# miavita.net
KiCad netlist of a schematic drawn in EAGLE
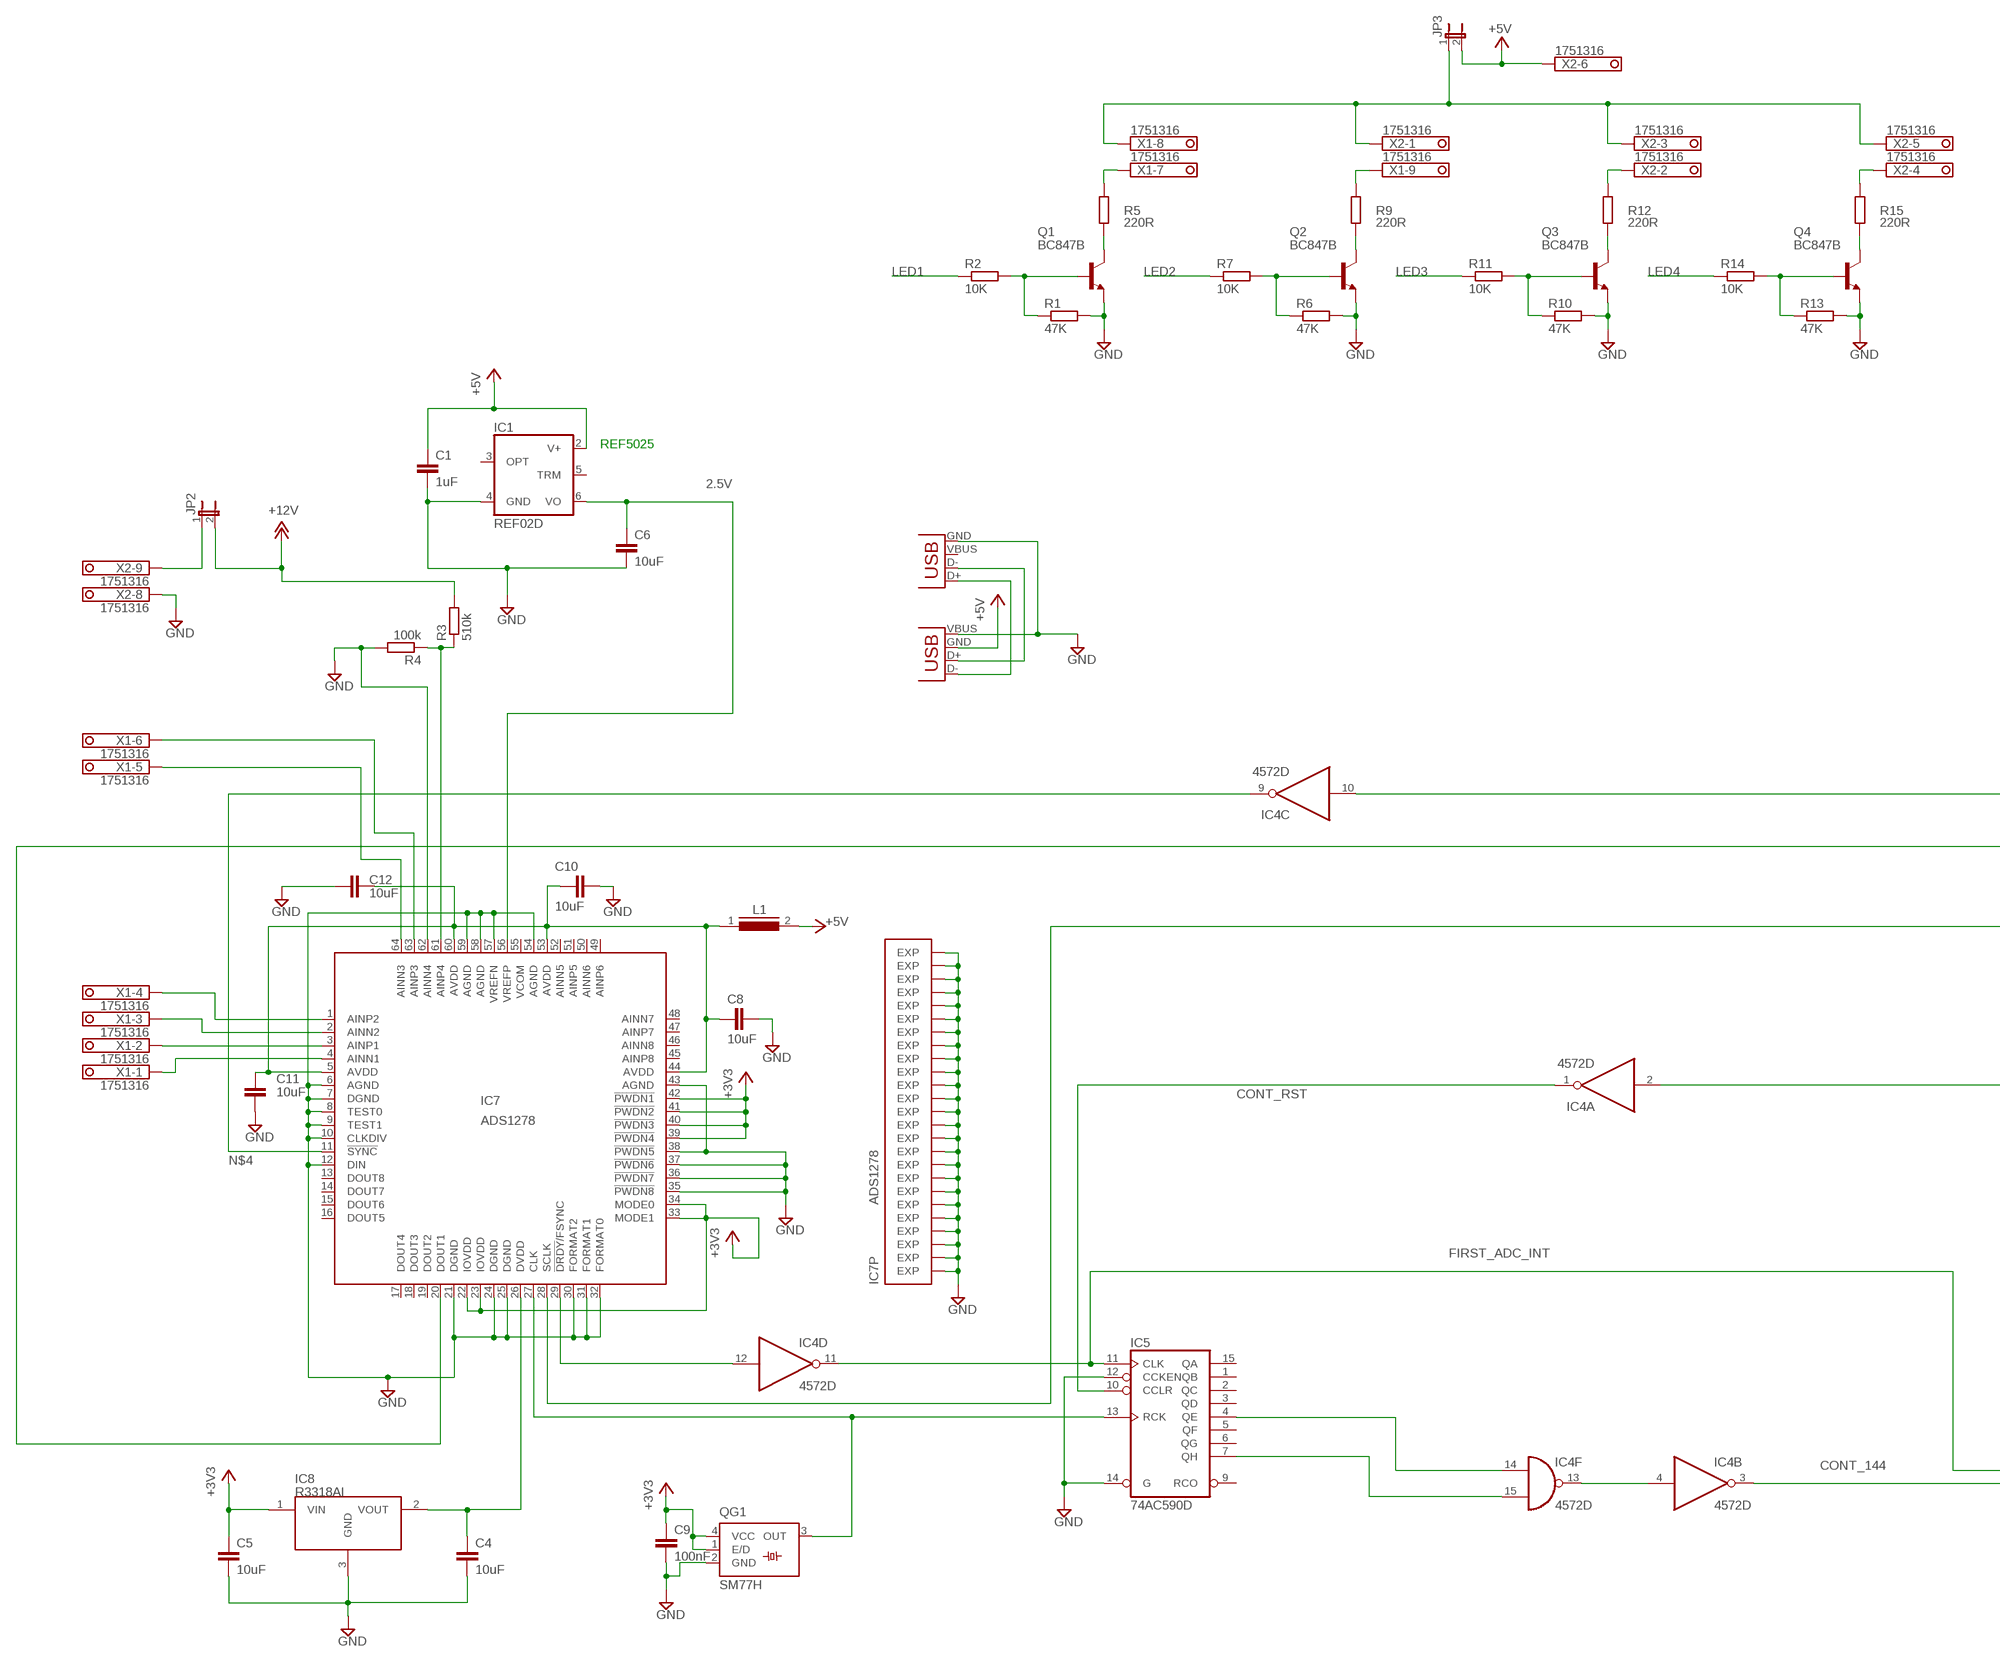
[diagram p0: schematic, sheet 1, part 1 of 2]
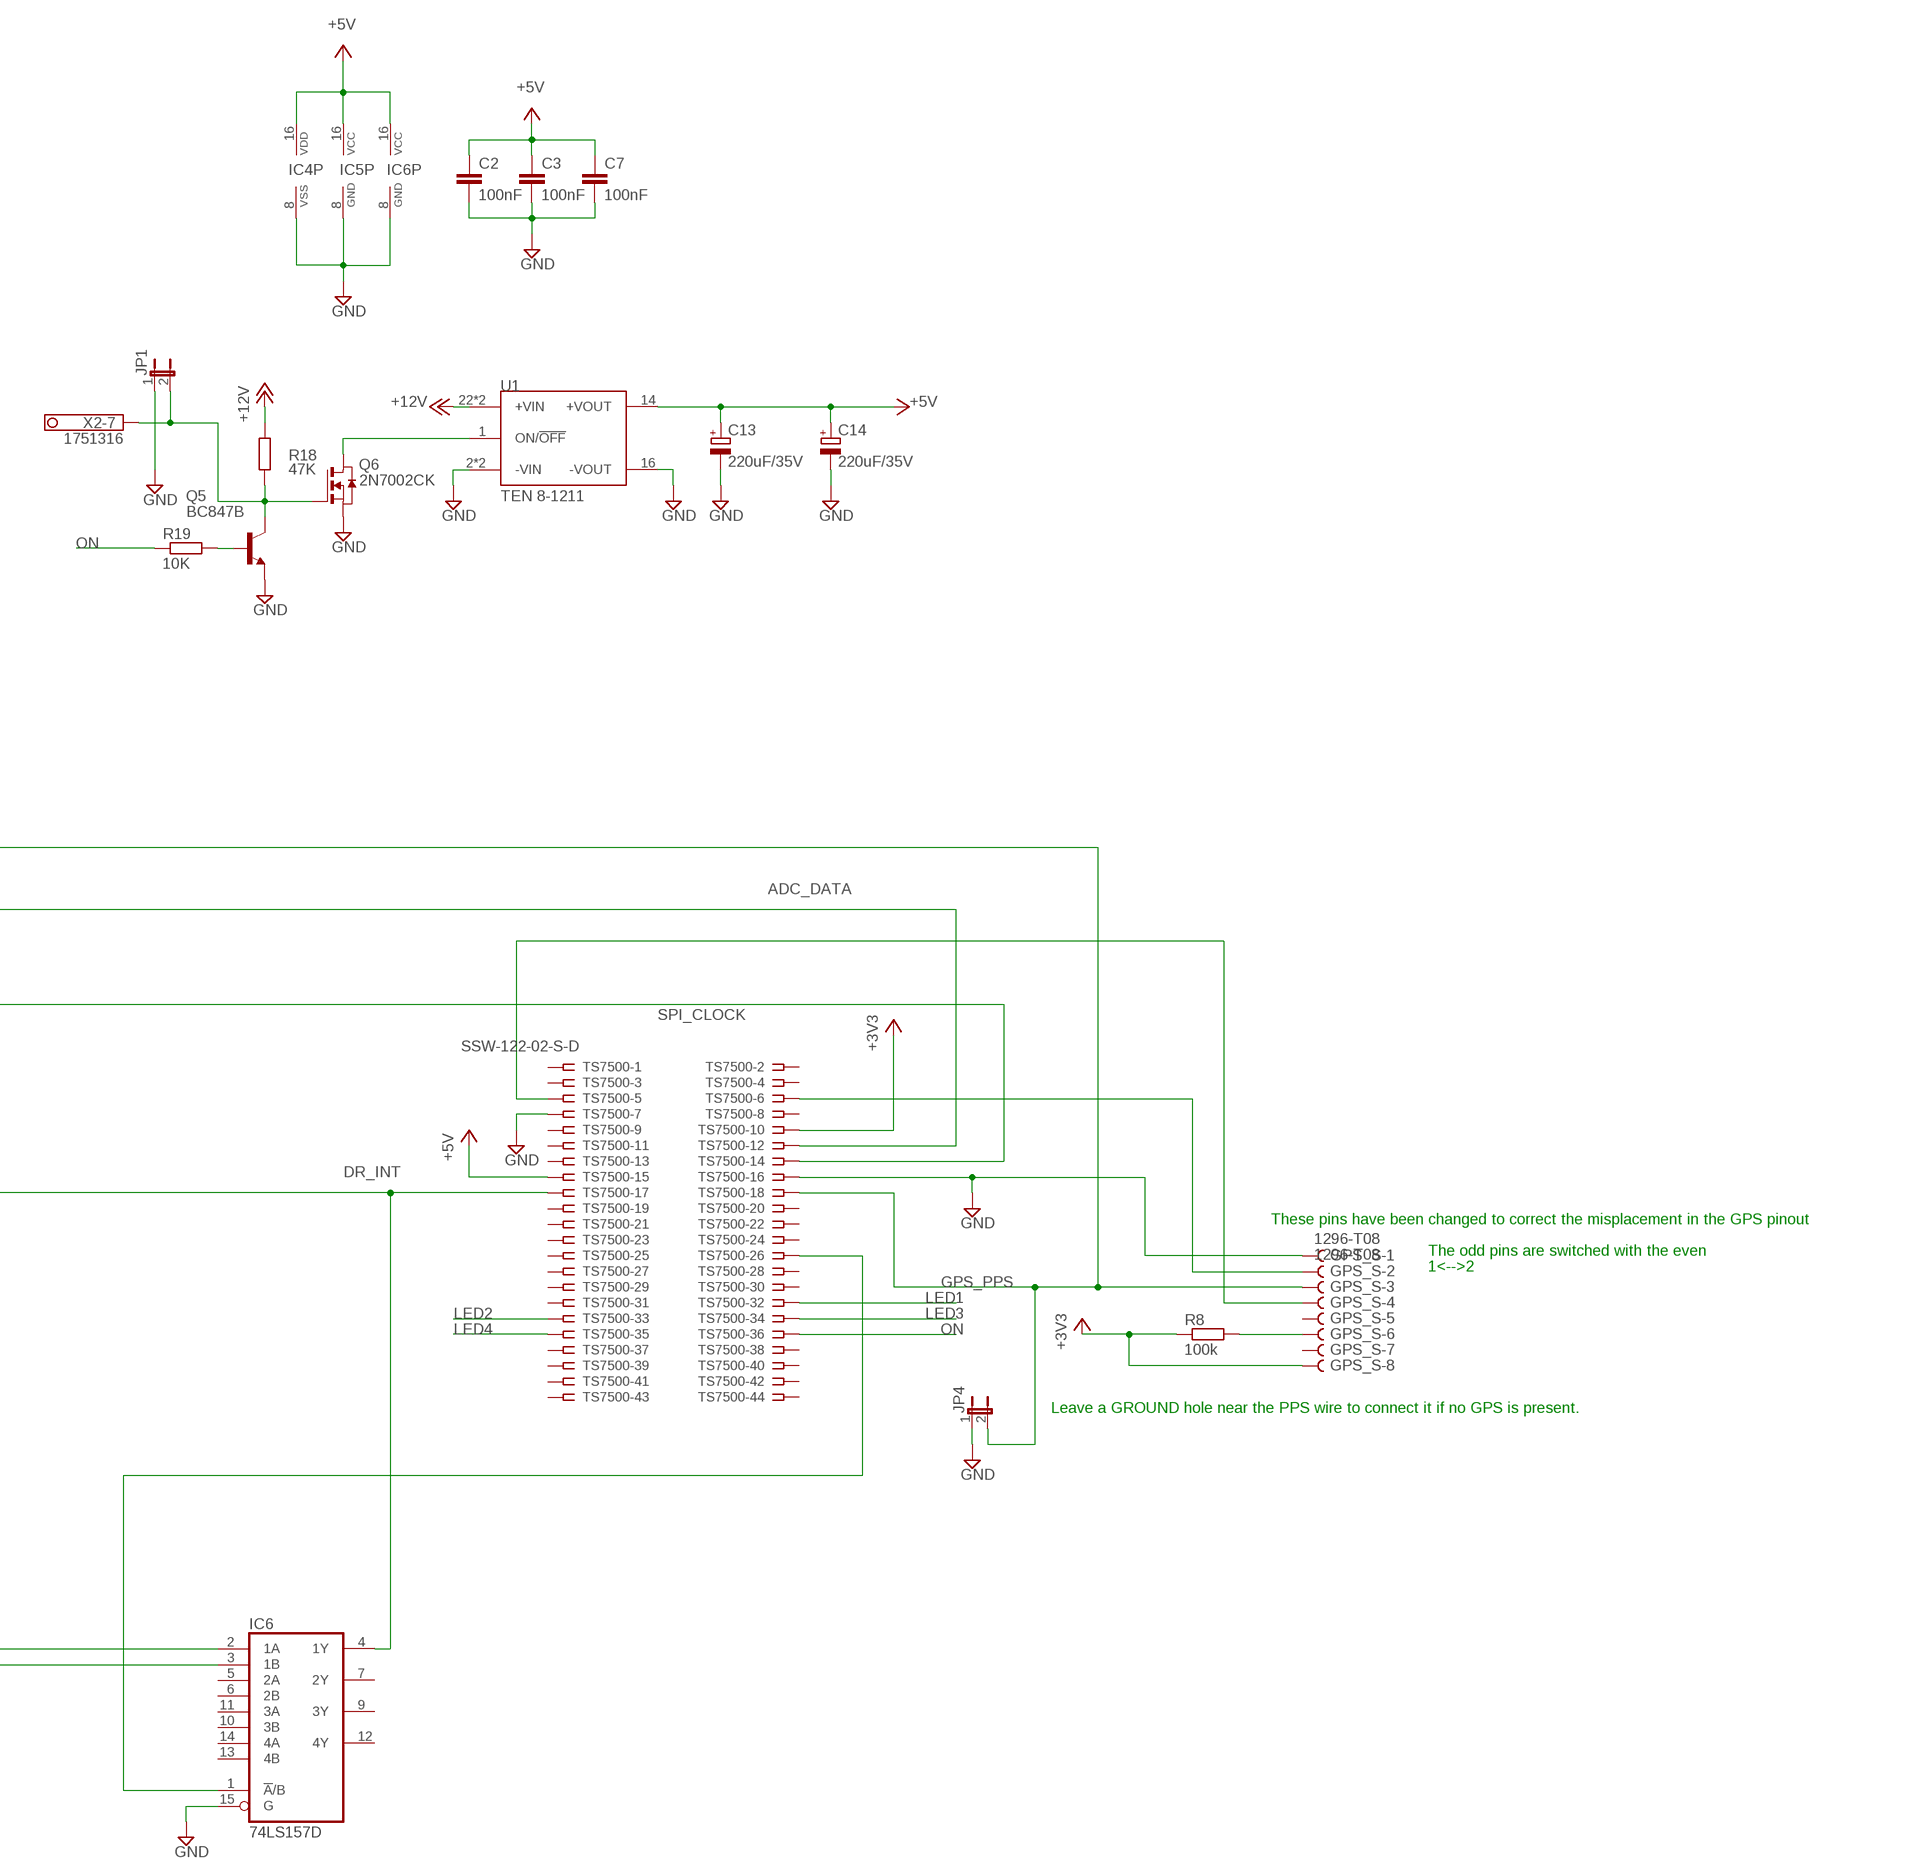
[diagram p1: schematic, sheet 1, part 2 of 2]

(export (version "E")
  (design (tool "Eeschema 10.0.6"))
  (components
    (comp (ref "C1")
      (value "1uF")
      (footprint "eagle-import:C0603")
      (libsource (lib "eagle-import") (part "C-EUC0603"))
    )
    (comp (ref "C2")
      (value "100nF")
      (footprint "eagle-import:C0603")
      (libsource (lib "eagle-import") (part "C-EUC0603"))
    )
    (comp (ref "C3")
      (value "100nF")
      (footprint "eagle-import:C0603")
      (libsource (lib "eagle-import") (part "C-EUC0603"))
    )
    (comp (ref "C4")
      (value "10uF")
      (footprint "eagle-import:C1210")
      (libsource (lib "eagle-import") (part "C-EUC1210"))
    )
    (comp (ref "C5")
      (value "10uF")
      (footprint "eagle-import:C1210")
      (libsource (lib "eagle-import") (part "C-EUC1210"))
    )
    (comp (ref "C6")
      (value "10uF")
      (footprint "eagle-import:C1210")
      (libsource (lib "eagle-import") (part "C-EUC1210"))
    )
    (comp (ref "C7")
      (value "100nF")
      (footprint "eagle-import:C0603")
      (libsource (lib "eagle-import") (part "C-EUC0603"))
    )
    (comp (ref "C8")
      (value "10uF")
      (footprint "eagle-import:C0805")
      (libsource (lib "eagle-import") (part "C-EUC0805"))
    )
    (comp (ref "C9")
      (value "100nF")
      (footprint "eagle-import:C0603")
      (libsource (lib "eagle-import") (part "C-EUC0603"))
    )
    (comp (ref "C10")
      (value "10uF")
      (footprint "eagle-import:C0805")
      (libsource (lib "eagle-import") (part "C-EUC0805"))
    )
    (comp (ref "C11")
      (value "10uF")
      (footprint "eagle-import:C0805")
      (libsource (lib "eagle-import") (part "C-EUC0805"))
    )
    (comp (ref "C12")
      (value "10uF")
      (footprint "eagle-import:C0805")
      (libsource (lib "eagle-import") (part "C-EUC0805"))
    )
    (comp (ref "C13")
      (value "220uF/35V")
      (footprint "eagle-import:UD-10X10_NICHICON")
      (libsource (lib "eagle-import") (part "CPOL-EUUD-10X10"))
    )
    (comp (ref "C14")
      (value "220uF/35V")
      (footprint "eagle-import:UD-10X10_NICHICON")
      (libsource (lib "eagle-import") (part "CPOL-EUUD-10X10"))
    )
    (comp (ref "GPS_S")
      (value "1296-T08")
      (footprint "eagle-import:1296-08")
      (libsource (lib "eagle-import") (part "1296-T08"))
    )
    (comp (ref "IC1")
      (value "REF02D")
      (footprint "eagle-import:SO08")
      (libsource (lib "eagle-import") (part "REF02D"))
    )
    (comp (ref "IC4")
      (value "4572D")
      (footprint "eagle-import:SO16")
      (libsource (lib "eagle-import") (part "4572D"))
    )
    (comp (ref "IC5")
      (value "74AC590D")
      (footprint "eagle-import:SO16")
      (libsource (lib "eagle-import") (part "74590DAC"))
    )
    (comp (ref "IC6")
      (value "74LS157D")
      (footprint "eagle-import:SO16")
      (libsource (lib "eagle-import") (part "74157DLS"))
    )
    (comp (ref "IC7")
      (value "ADS1278")
      (footprint "eagle-import:HTQFP-64-PAP")
      (fields (field (name "MPN") "ADS1278IPAPT"))
      (libsource (lib "eagle-import") (part "ADS1278"))
    )
    (comp (ref "IC8")
      (value "R3318AI")
      (footprint "eagle-import:SOT23")
      (libsource (lib "eagle-import") (part "MCP1525TTT-I/"))
    )
    (comp (ref "JP1")
      (value "JP1E")
      (footprint "eagle-import:JP1")
      (libsource (lib "eagle-import") (part "JP1E"))
    )
    (comp (ref "JP2")
      (value "JP1E")
      (footprint "eagle-import:JP1")
      (libsource (lib "eagle-import") (part "JP1E"))
    )
    (comp (ref "JP3")
      (value "JP1E")
      (footprint "eagle-import:JP1")
      (libsource (lib "eagle-import") (part "JP1E"))
    )
    (comp (ref "JP4")
      (value "JP1E")
      (footprint "eagle-import:JP1")
      (libsource (lib "eagle-import") (part "JP1E"))
    )
    (comp (ref "L1")
      (value "FAIR-RITE_2506031027Y0")
      (footprint "eagle-import:L0603")
      (libsource (lib "eagle-import") (part "FAIR-RITE_251027Y00603"))
    )
    (comp (ref "Q1")
      (value "BC847B")
      (footprint "eagle-import:SOT23")
      (libsource (lib "eagle-import") (part "BC847SMDBLT1"))
    )
    (comp (ref "Q2")
      (value "BC847B")
      (footprint "eagle-import:SOT23")
      (libsource (lib "eagle-import") (part "BC847SMDBLT1"))
    )
    (comp (ref "Q3")
      (value "BC847B")
      (footprint "eagle-import:SOT23")
      (libsource (lib "eagle-import") (part "BC847SMDBLT1"))
    )
    (comp (ref "Q4")
      (value "BC847B")
      (footprint "eagle-import:SOT23")
      (libsource (lib "eagle-import") (part "BC847SMDBLT1"))
    )
    (comp (ref "Q5")
      (value "BC847B")
      (footprint "eagle-import:SOT23")
      (libsource (lib "eagle-import") (part "BC847SMDBLT1"))
    )
    (comp (ref "Q6")
      (value "2N7002CK")
      (footprint "eagle-import:SOT23")
      (libsource (lib "eagle-import") (part "2N7002CK"))
    )
    (comp (ref "QG1")
      (value "SM77H")
      (footprint "eagle-import:SM77H")
      (libsource (lib "eagle-import") (part "SM77H"))
    )
    (comp (ref "R1")
      (value "47K")
      (footprint "eagle-import:R0603")
      (libsource (lib "eagle-import") (part "R-EU_R0603"))
    )
    (comp (ref "R2")
      (value "10K")
      (footprint "eagle-import:R0603")
      (libsource (lib "eagle-import") (part "R-EU_R0603"))
    )
    (comp (ref "R3")
      (value "510k")
      (footprint "eagle-import:R0603")
      (libsource (lib "eagle-import") (part "R-EU_R0603"))
    )
    (comp (ref "R4")
      (value "100k")
      (footprint "eagle-import:R0603")
      (libsource (lib "eagle-import") (part "R-EU_R0603"))
    )
    (comp (ref "R5")
      (value "220R")
      (footprint "eagle-import:R0603")
      (libsource (lib "eagle-import") (part "R-EU_R0603"))
    )
    (comp (ref "R6")
      (value "47K")
      (footprint "eagle-import:R0603")
      (libsource (lib "eagle-import") (part "R-EU_R0603"))
    )
    (comp (ref "R7")
      (value "10K")
      (footprint "eagle-import:R0603")
      (libsource (lib "eagle-import") (part "R-EU_R0603"))
    )
    (comp (ref "R8")
      (value "100k")
      (footprint "eagle-import:R0603")
      (libsource (lib "eagle-import") (part "R-EU_R0603"))
    )
    (comp (ref "R9")
      (value "220R")
      (footprint "eagle-import:R0603")
      (libsource (lib "eagle-import") (part "R-EU_R0603"))
    )
    (comp (ref "R10")
      (value "47K")
      (footprint "eagle-import:R0603")
      (libsource (lib "eagle-import") (part "R-EU_R0603"))
    )
    (comp (ref "R11")
      (value "10K")
      (footprint "eagle-import:R0603")
      (libsource (lib "eagle-import") (part "R-EU_R0603"))
    )
    (comp (ref "R12")
      (value "220R")
      (footprint "eagle-import:R0603")
      (libsource (lib "eagle-import") (part "R-EU_R0603"))
    )
    (comp (ref "R13")
      (value "47K")
      (footprint "eagle-import:R0603")
      (libsource (lib "eagle-import") (part "R-EU_R0603"))
    )
    (comp (ref "R14")
      (value "10K")
      (footprint "eagle-import:R0603")
      (libsource (lib "eagle-import") (part "R-EU_R0603"))
    )
    (comp (ref "R15")
      (value "220R")
      (footprint "eagle-import:R0603")
      (libsource (lib "eagle-import") (part "R-EU_R0603"))
    )
    (comp (ref "R18")
      (value "47K")
      (footprint "eagle-import:R0603")
      (libsource (lib "eagle-import") (part "R-EU_R0603"))
    )
    (comp (ref "R19")
      (value "10K")
      (footprint "eagle-import:R0603")
      (libsource (lib "eagle-import") (part "R-EU_R0603"))
    )
    (comp (ref "TS7500")
      (value "SSW-122-02-S-D")
      (footprint "eagle-import:SSW-122-02-S-D")
      (libsource (lib "eagle-import") (part "SSW-122-02-S-D"))
    )
    (comp (ref "U1")
      (value "TEN 8-1211")
      (footprint "eagle-import:TRACOPOWER_TEN-8-SERIES")
      (libsource (lib "eagle-import") (part "TRACOPOWER_TEN-8-1211"))
    )
    (comp (ref "USBA")
      (value "USB-A-H")
      (footprint "eagle-import:USB-A-H")
      (libsource (lib "eagle-import") (part "USB-A-H"))
    )
    (comp (ref "USBB")
      (value "USBPTH")
      (footprint "eagle-import:USB-B-PTH")
      (libsource (lib "eagle-import") (part "USBPTH"))
    )
    (comp (ref "X1")
      (value "1751316")
      (footprint "eagle-import:1751316")
      (libsource (lib "eagle-import") (part "1751316"))
    )
    (comp (ref "X2")
      (value "1751316")
      (footprint "eagle-import:1751316")
      (libsource (lib "eagle-import") (part "1751316"))
    )
  )
  (nets
    (net (code "1") (name "+3V3") (class "Default")
      (node (ref "C5") (pin "1") (pinfunction "1_1") (pintype "passive"))
      (node (ref "C9") (pin "1") (pinfunction "1_1") (pintype "passive"))
      (node (ref "GPS_S") (pin "8") (pinfunction "B_8") (pintype "passive"))
      (node (ref "IC7") (pin "22") (pinfunction "IOVDD_22") (pintype "power_in"))
      (node (ref "IC7") (pin "23") (pinfunction "IOVDD_23") (pintype "power_in"))
      (node (ref "IC7") (pin "33") (pinfunction "MODE1_33") (pintype "input"))
      (node (ref "IC7") (pin "34") (pinfunction "MODE0_34") (pintype "input"))
      (node (ref "IC7") (pin "39") (pinfunction "~{PWDN4}_39") (pintype "input"))
      (node (ref "IC7") (pin "40") (pinfunction "~{PWDN3}_40") (pintype "input"))
      (node (ref "IC7") (pin "41") (pinfunction "~{PWDN2}_41") (pintype "input"))
      (node (ref "IC7") (pin "42") (pinfunction "~{PWDN1}_42") (pintype "input"))
      (node (ref "IC8") (pin "1") (pinfunction "VIN_1") (pintype "power_in"))
      (node (ref "QG1") (pin "1") (pinfunction "E/D_1") (pintype "input"))
      (node (ref "QG1") (pin "4") (pinfunction "VCC_4") (pintype "power_in"))
      (node (ref "R8") (pin "1") (pinfunction "1_1") (pintype "passive"))
      (node (ref "TS7500") (pin "10") (pinfunction "1_10") (pintype "passive"))
    )
    (net (code "2") (name "+5V") (class "Default")
      (node (ref "C1") (pin "1") (pinfunction "1_1") (pintype "passive"))
      (node (ref "C13") (pin "+") (pinfunction "+_+") (pintype "passive"))
      (node (ref "C14") (pin "+") (pinfunction "+_+") (pintype "passive"))
      (node (ref "C2") (pin "1") (pinfunction "1_1") (pintype "passive"))
      (node (ref "C3") (pin "1") (pinfunction "1_1") (pintype "passive"))
      (node (ref "C7") (pin "1") (pinfunction "1_1") (pintype "passive"))
      (node (ref "IC1") (pin "2") (pinfunction "V+_2") (pintype "power_in"))
      (node (ref "IC4") (pin "16") (pinfunction "VDD_16") (pintype "power_in"))
      (node (ref "IC5") (pin "16") (pinfunction "VCC_16") (pintype "power_in"))
      (node (ref "IC6") (pin "16") (pinfunction "VCC_16") (pintype "power_in"))
      (node (ref "JP3") (pin "2") (pinfunction "2_2") (pintype "passive"))
      (node (ref "L1") (pin "2") (pinfunction "2_2") (pintype "passive"))
      (node (ref "TS7500") (pin "15") (pinfunction "1_15") (pintype "passive"))
      (node (ref "U1") (pin "14") (pinfunction "+VOUT_14") (pintype "bidirectional"))
      (node (ref "USBA") (pin "GND") (pinfunction "VBUS_GND") (pintype "bidirectional"))
      (node (ref "X2") (pin "6") (pinfunction "K_6") (pintype "passive"))
    )
    (net (code "3") (name "+12V") (class "Default")
      (node (ref "JP2") (pin "2") (pinfunction "2_2") (pintype "passive"))
      (node (ref "R18") (pin "1") (pinfunction "1_1") (pintype "passive"))
      (node (ref "R3") (pin "2") (pinfunction "2_2") (pintype "passive"))
      (node (ref "U1") (pin "22") (pinfunction "+VIN_22") (pintype "power_in"))
      (node (ref "U1") (pin "23") (pinfunction "+VIN_23") (pintype "power_in"))
    )
    (net (code "4") (name "/2.5V") (class "Default")
      (node (ref "C6") (pin "1") (pinfunction "1_1") (pintype "passive"))
      (node (ref "IC1") (pin "6") (pinfunction "VO_6") (pintype "output"))
      (node (ref "IC7") (pin "56") (pinfunction "VREFP_56") (pintype "input"))
    )
    (net (code "5") (name "/ADC_DATA") (class "Default")
      (node (ref "IC7") (pin "20") (pinfunction "DOUT1_20") (pintype "output"))
      (node (ref "TS7500") (pin "12") (pinfunction "1_12") (pintype "passive"))
    )
    (net (code "6") (name "/CONT_144") (class "Default")
      (node (ref "IC4") (pin "3") (pinfunction "O_3") (pintype "output"))
      (node (ref "IC6") (pin "3") (pinfunction "1B_3") (pintype "input"))
    )
    (net (code "7") (name "/CONT_RST") (class "Default")
      (node (ref "IC4") (pin "1") (pinfunction "O_1") (pintype "output"))
      (node (ref "IC5") (pin "10") (pinfunction "CCLR_10") (pintype "input"))
    )
    (net (code "8") (name "/DR_INT") (class "Default")
      (node (ref "IC4") (pin "2") (pinfunction "I_2") (pintype "input"))
      (node (ref "IC6") (pin "4") (pinfunction "1Y_4") (pintype "output"))
      (node (ref "TS7500") (pin "17") (pinfunction "1_17") (pintype "passive"))
    )
    (net (code "9") (name "/FIRST_ADC_INT") (class "Default")
      (node (ref "IC4") (pin "11") (pinfunction "O_11") (pintype "output"))
      (node (ref "IC5") (pin "11") (pinfunction "CLK_11") (pintype "input"))
      (node (ref "IC6") (pin "2") (pinfunction "1A_2") (pintype "input"))
    )
    (net (code "10") (name "/GPS_PPS") (class "Default")
      (node (ref "GPS_S") (pin "3") (pinfunction "B_3") (pintype "passive"))
      (node (ref "IC4") (pin "10") (pinfunction "I_10") (pintype "input"))
      (node (ref "JP4") (pin "2") (pinfunction "2_2") (pintype "passive"))
      (node (ref "TS7500") (pin "18") (pinfunction "1_18") (pintype "passive"))
    )
    (net (code "11") (name "/LED1") (class "Default")
      (node (ref "R2") (pin "1") (pinfunction "1_1") (pintype "passive"))
      (node (ref "TS7500") (pin "32") (pinfunction "1_32") (pintype "passive"))
    )
    (net (code "12") (name "/LED2") (class "Default")
      (node (ref "R7") (pin "1") (pinfunction "1_1") (pintype "passive"))
      (node (ref "TS7500") (pin "33") (pinfunction "1_33") (pintype "passive"))
    )
    (net (code "13") (name "/LED3") (class "Default")
      (node (ref "R11") (pin "1") (pinfunction "1_1") (pintype "passive"))
      (node (ref "TS7500") (pin "34") (pinfunction "1_34") (pintype "passive"))
    )
    (net (code "14") (name "/LED4") (class "Default")
      (node (ref "R14") (pin "1") (pinfunction "1_1") (pintype "passive"))
      (node (ref "TS7500") (pin "35") (pinfunction "1_35") (pintype "passive"))
    )
    (net (code "15") (name "/N$4") (class "Default")
      (node (ref "IC4") (pin "9") (pinfunction "O_9") (pintype "output"))
      (node (ref "IC7") (pin "11") (pinfunction "~{SYNC}_11") (pintype "input"))
    )
    (net (code "16") (name "/ON") (class "Default")
      (node (ref "R19") (pin "1") (pinfunction "1_1") (pintype "passive"))
      (node (ref "TS7500") (pin "36") (pinfunction "1_36") (pintype "passive"))
    )
    (net (code "17") (name "/SPI_CLOCK") (class "Default")
      (node (ref "IC7") (pin "28") (pinfunction "SCLK_28") (pintype "bidirectional"))
      (node (ref "TS7500") (pin "14") (pinfunction "1_14") (pintype "passive"))
    )
    (net (code "18") (name "GND") (class "Default")
      (node (ref "C1") (pin "2") (pinfunction "2_2") (pintype "passive"))
      (node (ref "C10") (pin "2") (pinfunction "2_2") (pintype "passive"))
      (node (ref "C11") (pin "2") (pinfunction "2_2") (pintype "passive"))
      (node (ref "C12") (pin "2") (pinfunction "2_2") (pintype "passive"))
      (node (ref "C13") (pin "-") (pinfunction "-_-") (pintype "passive"))
      (node (ref "C14") (pin "-") (pinfunction "-_-") (pintype "passive"))
      (node (ref "C2") (pin "2") (pinfunction "2_2") (pintype "passive"))
      (node (ref "C3") (pin "2") (pinfunction "2_2") (pintype "passive"))
      (node (ref "C4") (pin "2") (pinfunction "2_2") (pintype "passive"))
      (node (ref "C5") (pin "2") (pinfunction "2_2") (pintype "passive"))
      (node (ref "C6") (pin "2") (pinfunction "2_2") (pintype "passive"))
      (node (ref "C7") (pin "2") (pinfunction "2_2") (pintype "passive"))
      (node (ref "C8") (pin "2") (pinfunction "2_2") (pintype "passive"))
      (node (ref "C9") (pin "2") (pinfunction "2_2") (pintype "passive"))
      (node (ref "GPS_S") (pin "1") (pinfunction "B_1") (pintype "passive"))
      (node (ref "IC1") (pin "4") (pinfunction "GND_4") (pintype "power_in"))
      (node (ref "IC4") (pin "8") (pinfunction "VSS_8") (pintype "power_in"))
      (node (ref "IC5") (pin "12") (pinfunction "CCKEN_12") (pintype "input"))
      (node (ref "IC5") (pin "14") (pinfunction "G_14") (pintype "input"))
      (node (ref "IC5") (pin "8") (pinfunction "GND_8") (pintype "power_in"))
      (node (ref "IC6") (pin "15") (pinfunction "G_15") (pintype "input"))
      (node (ref "IC6") (pin "8") (pinfunction "GND_8") (pintype "power_in"))
      (node (ref "IC7") (pin "10") (pinfunction "CLKDIV_10") (pintype "input"))
      (node (ref "IC7") (pin "12") (pinfunction "DIN_12") (pintype "input"))
      (node (ref "IC7") (pin "21") (pinfunction "DGND_21") (pintype "power_in"))
      (node (ref "IC7") (pin "24") (pinfunction "DGND_24") (pintype "power_in"))
      (node (ref "IC7") (pin "25") (pinfunction "DGND_25") (pintype "power_in"))
      (node (ref "IC7") (pin "30") (pinfunction "FORMAT2_30") (pintype "input"))
      (node (ref "IC7") (pin "31") (pinfunction "FORMAT1_31") (pintype "input"))
      (node (ref "IC7") (pin "32") (pinfunction "FORMAT0_32") (pintype "input"))
      (node (ref "IC7") (pin "35") (pinfunction "~{PWDN8}_35") (pintype "input"))
      (node (ref "IC7") (pin "36") (pinfunction "~{PWDN7}_36") (pintype "input"))
      (node (ref "IC7") (pin "37") (pinfunction "~{PWDN6}_37") (pintype "input"))
      (node (ref "IC7") (pin "38") (pinfunction "~{PWDN5}_38") (pintype "input"))
      (node (ref "IC7") (pin "43") (pinfunction "AGND_43") (pintype "power_in"))
      (node (ref "IC7") (pin "54") (pinfunction "AGND_54") (pintype "power_in"))
      (node (ref "IC7") (pin "57") (pinfunction "VREFN_57") (pintype "input"))
      (node (ref "IC7") (pin "58") (pinfunction "AGND_58") (pintype "power_in"))
      (node (ref "IC7") (pin "59") (pinfunction "AGND_59") (pintype "power_in"))
      (node (ref "IC7") (pin "6") (pinfunction "AGND_6") (pintype "power_in"))
      (node (ref "IC7") (pin "62") (pinfunction "AINN4_62") (pintype "input"))
      (node (ref "IC7") (pin "7") (pinfunction "DGND_7") (pintype "power_in"))
      (node (ref "IC7") (pin "8") (pinfunction "TEST0_8") (pintype "input"))
      (node (ref "IC7") (pin "9") (pinfunction "TEST1_9") (pintype "input"))
      (node (ref "IC7") (pin "EXP1") (pinfunction "EXP_EXP1") (pintype "passive"))
      (node (ref "IC7") (pin "EXP10") (pinfunction "EXP_EXP10") (pintype "passive"))
      (node (ref "IC7") (pin "EXP11") (pinfunction "EXP_EXP11") (pintype "passive"))
      (node (ref "IC7") (pin "EXP12") (pinfunction "EXP_EXP12") (pintype "passive"))
      (node (ref "IC7") (pin "EXP13") (pinfunction "EXP_EXP13") (pintype "passive"))
      (node (ref "IC7") (pin "EXP14") (pinfunction "EXP_EXP14") (pintype "passive"))
      (node (ref "IC7") (pin "EXP15") (pinfunction "EXP_EXP15") (pintype "passive"))
      (node (ref "IC7") (pin "EXP16") (pinfunction "EXP_EXP16") (pintype "passive"))
      (node (ref "IC7") (pin "EXP17") (pinfunction "EXP_EXP17") (pintype "passive"))
      (node (ref "IC7") (pin "EXP18") (pinfunction "EXP_EXP18") (pintype "passive"))
      (node (ref "IC7") (pin "EXP19") (pinfunction "EXP_EXP19") (pintype "passive"))
      (node (ref "IC7") (pin "EXP2") (pinfunction "EXP_EXP2") (pintype "passive"))
      (node (ref "IC7") (pin "EXP20") (pinfunction "EXP_EXP20") (pintype "passive"))
      (node (ref "IC7") (pin "EXP21") (pinfunction "EXP_EXP21") (pintype "passive"))
      (node (ref "IC7") (pin "EXP22") (pinfunction "EXP_EXP22") (pintype "passive"))
      (node (ref "IC7") (pin "EXP23") (pinfunction "EXP_EXP23") (pintype "passive"))
      (node (ref "IC7") (pin "EXP24") (pinfunction "EXP_EXP24") (pintype "passive"))
      (node (ref "IC7") (pin "EXP25") (pinfunction "EXP_EXP25") (pintype "passive"))
      (node (ref "IC7") (pin "EXP3") (pinfunction "EXP_EXP3") (pintype "passive"))
      (node (ref "IC7") (pin "EXP4") (pinfunction "EXP_EXP4") (pintype "passive"))
      (node (ref "IC7") (pin "EXP5") (pinfunction "EXP_EXP5") (pintype "passive"))
      (node (ref "IC7") (pin "EXP6") (pinfunction "EXP_EXP6") (pintype "passive"))
      (node (ref "IC7") (pin "EXP7") (pinfunction "EXP_EXP7") (pintype "passive"))
      (node (ref "IC7") (pin "EXP8") (pinfunction "EXP_EXP8") (pintype "passive"))
      (node (ref "IC7") (pin "EXP9") (pinfunction "EXP_EXP9") (pintype "passive"))
      (node (ref "IC8") (pin "3") (pinfunction "GND_3") (pintype "power_in"))
      (node (ref "JP1") (pin "1") (pinfunction "1_1") (pintype "passive"))
      (node (ref "JP4") (pin "1") (pinfunction "1_1") (pintype "passive"))
      (node (ref "Q1") (pin "2") (pinfunction "E_2") (pintype "passive"))
      (node (ref "Q2") (pin "2") (pinfunction "E_2") (pintype "passive"))
      (node (ref "Q3") (pin "2") (pinfunction "E_2") (pintype "passive"))
      (node (ref "Q4") (pin "2") (pinfunction "E_2") (pintype "passive"))
      (node (ref "Q5") (pin "2") (pinfunction "E_2") (pintype "passive"))
      (node (ref "Q6") (pin "2") (pinfunction "S_2") (pintype "passive"))
      (node (ref "QG1") (pin "2") (pinfunction "GND_2") (pintype "power_in"))
      (node (ref "R1") (pin "2") (pinfunction "2_2") (pintype "passive"))
      (node (ref "R10") (pin "2") (pinfunction "2_2") (pintype "passive"))
      (node (ref "R13") (pin "2") (pinfunction "2_2") (pintype "passive"))
      (node (ref "R4") (pin "2") (pinfunction "2_2") (pintype "passive"))
      (node (ref "R6") (pin "2") (pinfunction "2_2") (pintype "passive"))
      (node (ref "TS7500") (pin "16") (pinfunction "1_16") (pintype "passive"))
      (node (ref "TS7500") (pin "7") (pinfunction "1_7") (pintype "passive"))
      (node (ref "U1") (pin "16") (pinfunction "-VOUT_16") (pintype "bidirectional"))
      (node (ref "U1") (pin "2") (pinfunction "-VIN_2") (pintype "bidirectional"))
      (node (ref "U1") (pin "3") (pinfunction "-VIN_3") (pintype "bidirectional"))
      (node (ref "USBA") (pin "VBUS") (pinfunction "GND_VBUS") (pintype "bidirectional"))
      (node (ref "USBB") (pin "GND") (pinfunction "GND_GND") (pintype "bidirectional"))
      (node (ref "X2") (pin "8") (pinfunction "K_8") (pintype "passive"))
    )
    (net (code "19") (name "Net-(C10-Pad1)") (class "Default")
      (node (ref "C10") (pin "1") (pinfunction "1_1") (pintype "passive"))
      (node (ref "C11") (pin "1") (pinfunction "1_1") (pintype "passive"))
      (node (ref "C12") (pin "1") (pinfunction "1_1") (pintype "passive"))
      (node (ref "C8") (pin "1") (pinfunction "1_1") (pintype "passive"))
      (node (ref "IC7") (pin "44") (pinfunction "AVDD_44") (pintype "power_in"))
      (node (ref "IC7") (pin "5") (pinfunction "AVDD_5") (pintype "power_in"))
      (node (ref "IC7") (pin "53") (pinfunction "AVDD_53") (pintype "power_in"))
      (node (ref "IC7") (pin "60") (pinfunction "AVDD_60") (pintype "power_in"))
      (node (ref "L1") (pin "1") (pinfunction "1_1") (pintype "passive"))
    )
    (net (code "20") (name "Net-(GPS_SB-B)") (class "Default")
      (node (ref "GPS_S") (pin "2") (pinfunction "B_2") (pintype "passive"))
      (node (ref "TS7500") (pin "6") (pinfunction "1_6") (pintype "passive"))
    )
    (net (code "21") (name "Net-(GPS_SD-B)") (class "Default")
      (node (ref "GPS_S") (pin "4") (pinfunction "B_4") (pintype "passive"))
      (node (ref "TS7500") (pin "5") (pinfunction "1_5") (pintype "passive"))
    )
    (net (code "22") (name "Net-(GPS_SF-B)") (class "Default")
      (node (ref "GPS_S") (pin "6") (pinfunction "B_6") (pintype "passive"))
      (node (ref "R8") (pin "2") (pinfunction "2_2") (pintype "passive"))
    )
    (net (code "23") (name "Net-(IC4B-I)") (class "Default")
      (node (ref "IC4") (pin "13") (pinfunction "O_13") (pintype "output"))
      (node (ref "IC4") (pin "4") (pinfunction "I_4") (pintype "input"))
    )
    (net (code "24") (name "Net-(IC4D-I)") (class "Default")
      (node (ref "IC4") (pin "12") (pinfunction "I_12") (pintype "input"))
      (node (ref "IC7") (pin "29") (pinfunction "~{DRDY}/FSYNC_29") (pintype "bidirectional"))
    )
    (net (code "25") (name "Net-(IC4F-I0)") (class "Default")
      (node (ref "IC4") (pin "14") (pinfunction "I0_14") (pintype "input"))
      (node (ref "IC5") (pin "4") (pinfunction "QE_4") (pintype "tri_state"))
    )
    (net (code "26") (name "Net-(IC4F-I1)") (class "Default")
      (node (ref "IC4") (pin "15") (pinfunction "I1_15") (pintype "input"))
      (node (ref "IC5") (pin "7") (pinfunction "QH_7") (pintype "tri_state"))
    )
    (net (code "27") (name "Net-(IC5A-RCK)") (class "Default")
      (node (ref "IC5") (pin "13") (pinfunction "RCK_13") (pintype "input"))
      (node (ref "IC7") (pin "27") (pinfunction "CLK_27") (pintype "input"))
      (node (ref "QG1") (pin "3") (pinfunction "OUT_3") (pintype "output"))
    )
    (net (code "28") (name "Net-(IC6A-~{A}{slash}B)") (class "Default")
      (node (ref "IC6") (pin "1") (pinfunction "~{A}/B_1") (pintype "input"))
      (node (ref "TS7500") (pin "26") (pinfunction "1_26") (pintype "passive"))
    )
    (net (code "29") (name "Net-(IC7A-AINN1)") (class "Default")
      (node (ref "IC7") (pin "4") (pinfunction "AINN1_4") (pintype "input"))
      (node (ref "X1") (pin "1") (pinfunction "K_1") (pintype "passive"))
    )
    (net (code "30") (name "Net-(IC7A-AINN2)") (class "Default")
      (node (ref "IC7") (pin "2") (pinfunction "AINN2_2") (pintype "input"))
      (node (ref "X1") (pin "3") (pinfunction "K_3") (pintype "passive"))
    )
    (net (code "31") (name "Net-(IC7A-AINN3)") (class "Default")
      (node (ref "IC7") (pin "64") (pinfunction "AINN3_64") (pintype "input"))
      (node (ref "X1") (pin "5") (pinfunction "K_5") (pintype "passive"))
    )
    (net (code "32") (name "Net-(IC7A-AINP1)") (class "Default")
      (node (ref "IC7") (pin "3") (pinfunction "AINP1_3") (pintype "input"))
      (node (ref "X1") (pin "2") (pinfunction "K_2") (pintype "passive"))
    )
    (net (code "33") (name "Net-(IC7A-AINP2)") (class "Default")
      (node (ref "IC7") (pin "1") (pinfunction "AINP2_1") (pintype "input"))
      (node (ref "X1") (pin "4") (pinfunction "K_4") (pintype "passive"))
    )
    (net (code "34") (name "Net-(IC7A-AINP3)") (class "Default")
      (node (ref "IC7") (pin "63") (pinfunction "AINP3_63") (pintype "input"))
      (node (ref "X1") (pin "6") (pinfunction "K_6") (pintype "passive"))
    )
    (net (code "35") (name "Net-(IC7A-AINP4)") (class "Default")
      (node (ref "IC7") (pin "61") (pinfunction "AINP4_61") (pintype "input"))
      (node (ref "R3") (pin "1") (pinfunction "1_1") (pintype "passive"))
      (node (ref "R4") (pin "1") (pinfunction "1_1") (pintype "passive"))
    )
    (net (code "36") (name "Net-(IC7A-DVDD)") (class "Default")
      (node (ref "C4") (pin "1") (pinfunction "1_1") (pintype "passive"))
      (node (ref "IC7") (pin "26") (pinfunction "DVDD_26") (pintype "power_in"))
      (node (ref "IC8") (pin "2") (pinfunction "VOUT_2") (pintype "power_in"))
    )
    (net (code "37") (name "Net-(Q1-B)") (class "Default")
      (node (ref "Q1") (pin "1") (pinfunction "B_1") (pintype "passive"))
      (node (ref "R1") (pin "1") (pinfunction "1_1") (pintype "passive"))
      (node (ref "R2") (pin "2") (pinfunction "2_2") (pintype "passive"))
    )
    (net (code "38") (name "Net-(Q1-C)") (class "Default")
      (node (ref "Q1") (pin "3") (pinfunction "C_3") (pintype "passive"))
      (node (ref "R5") (pin "1") (pinfunction "1_1") (pintype "passive"))
    )
    (net (code "39") (name "Net-(Q2-B)") (class "Default")
      (node (ref "Q2") (pin "1") (pinfunction "B_1") (pintype "passive"))
      (node (ref "R6") (pin "1") (pinfunction "1_1") (pintype "passive"))
      (node (ref "R7") (pin "2") (pinfunction "2_2") (pintype "passive"))
    )
    (net (code "40") (name "Net-(Q2-C)") (class "Default")
      (node (ref "Q2") (pin "3") (pinfunction "C_3") (pintype "passive"))
      (node (ref "R9") (pin "1") (pinfunction "1_1") (pintype "passive"))
    )
    (net (code "41") (name "Net-(Q3-B)") (class "Default")
      (node (ref "Q3") (pin "1") (pinfunction "B_1") (pintype "passive"))
      (node (ref "R10") (pin "1") (pinfunction "1_1") (pintype "passive"))
      (node (ref "R11") (pin "2") (pinfunction "2_2") (pintype "passive"))
    )
    (net (code "42") (name "Net-(Q3-C)") (class "Default")
      (node (ref "Q3") (pin "3") (pinfunction "C_3") (pintype "passive"))
      (node (ref "R12") (pin "1") (pinfunction "1_1") (pintype "passive"))
    )
    (net (code "43") (name "Net-(Q4-B)") (class "Default")
      (node (ref "Q4") (pin "1") (pinfunction "B_1") (pintype "passive"))
      (node (ref "R13") (pin "1") (pinfunction "1_1") (pintype "passive"))
      (node (ref "R14") (pin "2") (pinfunction "2_2") (pintype "passive"))
    )
    (net (code "44") (name "Net-(Q4-C)") (class "Default")
      (node (ref "Q4") (pin "3") (pinfunction "C_3") (pintype "passive"))
      (node (ref "R15") (pin "1") (pinfunction "1_1") (pintype "passive"))
    )
    (net (code "45") (name "Net-(Q5-B)") (class "Default")
      (node (ref "Q5") (pin "1") (pinfunction "B_1") (pintype "passive"))
      (node (ref "R19") (pin "2") (pinfunction "2_2") (pintype "passive"))
    )
    (net (code "46") (name "Net-(Q5-C)") (class "Default")
      (node (ref "JP1") (pin "2") (pinfunction "2_2") (pintype "passive"))
      (node (ref "Q5") (pin "3") (pinfunction "C_3") (pintype "passive"))
      (node (ref "Q6") (pin "1") (pinfunction "G_1") (pintype "passive"))
      (node (ref "R18") (pin "2") (pinfunction "2_2") (pintype "passive"))
      (node (ref "X2") (pin "7") (pinfunction "K_7") (pintype "passive"))
    )
    (net (code "47") (name "Net-(Q6-D)") (class "Default")
      (node (ref "Q6") (pin "3") (pinfunction "D_3") (pintype "passive"))
      (node (ref "U1") (pin "1") (pinfunction "ON/~{OFF}_1") (pintype "bidirectional"))
    )
    (net (code "48") (name "Net-(USBA-D+)") (class "Default")
      (node (ref "USBA") (pin "D-") (pinfunction "D+_D-") (pintype "bidirectional"))
      (node (ref "USBB") (pin "D+") (pinfunction "D+_D+") (pintype "bidirectional"))
    )
    (net (code "49") (name "Net-(USBA-D-)") (class "Default")
      (node (ref "USBA") (pin "D+") (pinfunction "D-_D+") (pintype "bidirectional"))
      (node (ref "USBB") (pin "D-") (pinfunction "D-_D-") (pintype "bidirectional"))
    )
    (net (code "50") (name "Net-(X1G-K)") (class "Default")
      (node (ref "R5") (pin "2") (pinfunction "2_2") (pintype "passive"))
      (node (ref "X1") (pin "7") (pinfunction "K_7") (pintype "passive"))
    )
    (net (code "51") (name "Net-(X1H-K)") (class "Default")
      (node (ref "JP3") (pin "1") (pinfunction "1_1") (pintype "passive"))
      (node (ref "X1") (pin "8") (pinfunction "K_8") (pintype "passive"))
      (node (ref "X2") (pin "1") (pinfunction "K_1") (pintype "passive"))
      (node (ref "X2") (pin "3") (pinfunction "K_3") (pintype "passive"))
      (node (ref "X2") (pin "5") (pinfunction "K_5") (pintype "passive"))
    )
    (net (code "52") (name "Net-(X1I-K)") (class "Default")
      (node (ref "R9") (pin "2") (pinfunction "2_2") (pintype "passive"))
      (node (ref "X1") (pin "9") (pinfunction "K_9") (pintype "passive"))
    )
    (net (code "53") (name "Net-(X2B-K)") (class "Default")
      (node (ref "R12") (pin "2") (pinfunction "2_2") (pintype "passive"))
      (node (ref "X2") (pin "2") (pinfunction "K_2") (pintype "passive"))
    )
    (net (code "54") (name "Net-(X2D-K)") (class "Default")
      (node (ref "R15") (pin "2") (pinfunction "2_2") (pintype "passive"))
      (node (ref "X2") (pin "4") (pinfunction "K_4") (pintype "passive"))
    )
    (net (code "55") (name "Net-(X2I-K)") (class "Default")
      (node (ref "JP2") (pin "1") (pinfunction "1_1") (pintype "passive"))
      (node (ref "X2") (pin "9") (pinfunction "K_9") (pintype "passive"))
    )
    (net (code "56") (name "unconnected-(GPS_SE-B-Pad5)") (class "Default")
      (node (ref "GPS_S") (pin "5") (pinfunction "B_5") (pintype "passive"))
    )
    (net (code "57") (name "unconnected-(GPS_SG-B-Pad7)") (class "Default")
      (node (ref "GPS_S") (pin "7") (pinfunction "B_7") (pintype "passive"))
    )
    (net (code "58") (name "unconnected-(IC1-OPT-Pad3)") (class "Default")
      (node (ref "IC1") (pin "3") (pinfunction "OPT_3") (pintype "output"))
    )
    (net (code "59") (name "unconnected-(IC1-TRM-Pad5)") (class "Default")
      (node (ref "IC1") (pin "5") (pinfunction "TRM_5") (pintype "input"))
    )
    (net (code "60") (name "unconnected-(IC5A-QA-Pad15)") (class "Default")
      (node (ref "IC5") (pin "15") (pinfunction "QA_15") (pintype "tri_state"))
    )
    (net (code "61") (name "unconnected-(IC5A-QB-Pad1)") (class "Default")
      (node (ref "IC5") (pin "1") (pinfunction "QB_1") (pintype "tri_state"))
    )
    (net (code "62") (name "unconnected-(IC5A-QC-Pad2)") (class "Default")
      (node (ref "IC5") (pin "2") (pinfunction "QC_2") (pintype "tri_state"))
    )
    (net (code "63") (name "unconnected-(IC5A-QD-Pad3)") (class "Default")
      (node (ref "IC5") (pin "3") (pinfunction "QD_3") (pintype "tri_state"))
    )
    (net (code "64") (name "unconnected-(IC5A-QF-Pad5)") (class "Default")
      (node (ref "IC5") (pin "5") (pinfunction "QF_5") (pintype "tri_state"))
    )
    (net (code "65") (name "unconnected-(IC5A-QG-Pad6)") (class "Default")
      (node (ref "IC5") (pin "6") (pinfunction "QG_6") (pintype "tri_state"))
    )
    (net (code "66") (name "unconnected-(IC5A-RCO-Pad9)") (class "Default")
      (node (ref "IC5") (pin "9") (pinfunction "RCO_9") (pintype "output"))
    )
    (net (code "67") (name "unconnected-(IC6A-2A-Pad5)") (class "Default")
      (node (ref "IC6") (pin "5") (pinfunction "2A_5") (pintype "input"))
    )
    (net (code "68") (name "unconnected-(IC6A-2B-Pad6)") (class "Default")
      (node (ref "IC6") (pin "6") (pinfunction "2B_6") (pintype "input"))
    )
    (net (code "69") (name "unconnected-(IC6A-2Y-Pad7)") (class "Default")
      (node (ref "IC6") (pin "7") (pinfunction "2Y_7") (pintype "output"))
    )
    (net (code "70") (name "unconnected-(IC6A-3A-Pad11)") (class "Default")
      (node (ref "IC6") (pin "11") (pinfunction "3A_11") (pintype "input"))
    )
    (net (code "71") (name "unconnected-(IC6A-3B-Pad10)") (class "Default")
      (node (ref "IC6") (pin "10") (pinfunction "3B_10") (pintype "input"))
    )
    (net (code "72") (name "unconnected-(IC6A-3Y-Pad9)") (class "Default")
      (node (ref "IC6") (pin "9") (pinfunction "3Y_9") (pintype "output"))
    )
    (net (code "73") (name "unconnected-(IC6A-4A-Pad14)") (class "Default")
      (node (ref "IC6") (pin "14") (pinfunction "4A_14") (pintype "input"))
    )
    (net (code "74") (name "unconnected-(IC6A-4B-Pad13)") (class "Default")
      (node (ref "IC6") (pin "13") (pinfunction "4B_13") (pintype "input"))
    )
    (net (code "75") (name "unconnected-(IC6A-4Y-Pad12)") (class "Default")
      (node (ref "IC6") (pin "12") (pinfunction "4Y_12") (pintype "output"))
    )
    (net (code "76") (name "unconnected-(IC7A-AINN5-Pad52)") (class "Default")
      (node (ref "IC7") (pin "52") (pinfunction "AINN5_52") (pintype "input"))
    )
    (net (code "77") (name "unconnected-(IC7A-AINN6-Pad50)") (class "Default")
      (node (ref "IC7") (pin "50") (pinfunction "AINN6_50") (pintype "input"))
    )
    (net (code "78") (name "unconnected-(IC7A-AINN7-Pad48)") (class "Default")
      (node (ref "IC7") (pin "48") (pinfunction "AINN7_48") (pintype "input"))
    )
    (net (code "79") (name "unconnected-(IC7A-AINN8-Pad46)") (class "Default")
      (node (ref "IC7") (pin "46") (pinfunction "AINN8_46") (pintype "input"))
    )
    (net (code "80") (name "unconnected-(IC7A-AINP5-Pad51)") (class "Default")
      (node (ref "IC7") (pin "51") (pinfunction "AINP5_51") (pintype "input"))
    )
    (net (code "81") (name "unconnected-(IC7A-AINP6-Pad49)") (class "Default")
      (node (ref "IC7") (pin "49") (pinfunction "AINP6_49") (pintype "input"))
    )
    (net (code "82") (name "unconnected-(IC7A-AINP7-Pad47)") (class "Default")
      (node (ref "IC7") (pin "47") (pinfunction "AINP7_47") (pintype "input"))
    )
    (net (code "83") (name "unconnected-(IC7A-AINP8-Pad45)") (class "Default")
      (node (ref "IC7") (pin "45") (pinfunction "AINP8_45") (pintype "input"))
    )
    (net (code "84") (name "unconnected-(IC7A-DOUT2-Pad19)") (class "Default")
      (node (ref "IC7") (pin "19") (pinfunction "DOUT2_19") (pintype "output"))
    )
    (net (code "85") (name "unconnected-(IC7A-DOUT3-Pad18)") (class "Default")
      (node (ref "IC7") (pin "18") (pinfunction "DOUT3_18") (pintype "output"))
    )
    (net (code "86") (name "unconnected-(IC7A-DOUT4-Pad17)") (class "Default")
      (node (ref "IC7") (pin "17") (pinfunction "DOUT4_17") (pintype "output"))
    )
    (net (code "87") (name "unconnected-(IC7A-DOUT5-Pad16)") (class "Default")
      (node (ref "IC7") (pin "16") (pinfunction "DOUT5_16") (pintype "output"))
    )
    (net (code "88") (name "unconnected-(IC7A-DOUT6-Pad15)") (class "Default")
      (node (ref "IC7") (pin "15") (pinfunction "DOUT6_15") (pintype "output"))
    )
    (net (code "89") (name "unconnected-(IC7A-DOUT7-Pad14)") (class "Default")
      (node (ref "IC7") (pin "14") (pinfunction "DOUT7_14") (pintype "output"))
    )
    (net (code "90") (name "unconnected-(IC7A-DOUT8-Pad13)") (class "Default")
      (node (ref "IC7") (pin "13") (pinfunction "DOUT8_13") (pintype "output"))
    )
    (net (code "91") (name "unconnected-(IC7A-VCOM-Pad55)") (class "Default")
      (node (ref "IC7") (pin "55") (pinfunction "VCOM_55") (pintype "output"))
    )
    (net (code "92") (name "unconnected-(TS7500-Pad1)") (class "Default")
      (node (ref "TS7500") (pin "1") (pinfunction "1_1") (pintype "passive"))
    )
    (net (code "93") (name "unconnected-(TS7500AE-1-Pad37)") (class "Default")
      (node (ref "TS7500") (pin "37") (pinfunction "1_37") (pintype "passive"))
    )
    (net (code "94") (name "unconnected-(TS7500AF-1-Pad38)") (class "Default")
      (node (ref "TS7500") (pin "38") (pinfunction "1_38") (pintype "passive"))
    )
    (net (code "95") (name "unconnected-(TS7500AG-1-Pad39)") (class "Default")
      (node (ref "TS7500") (pin "39") (pinfunction "1_39") (pintype "passive"))
    )
    (net (code "96") (name "unconnected-(TS7500AH-1-Pad4)") (class "Default")
      (node (ref "TS7500") (pin "4") (pinfunction "1_4") (pintype "passive"))
    )
    (net (code "97") (name "unconnected-(TS7500AI-1-Pad40)") (class "Default")
      (node (ref "TS7500") (pin "40") (pinfunction "1_40") (pintype "passive"))
    )
    (net (code "98") (name "unconnected-(TS7500AJ-1-Pad41)") (class "Default")
      (node (ref "TS7500") (pin "41") (pinfunction "1_41") (pintype "passive"))
    )
    (net (code "99") (name "unconnected-(TS7500AK-1-Pad42)") (class "Default")
      (node (ref "TS7500") (pin "42") (pinfunction "1_42") (pintype "passive"))
    )
    (net (code "100") (name "unconnected-(TS7500AL-1-Pad43)") (class "Default")
      (node (ref "TS7500") (pin "43") (pinfunction "1_43") (pintype "passive"))
    )
    (net (code "101") (name "unconnected-(TS7500AM-1-Pad44)") (class "Default")
      (node (ref "TS7500") (pin "44") (pinfunction "1_44") (pintype "passive"))
    )
    (net (code "102") (name "unconnected-(TS7500AQ-1-Pad8)") (class "Default")
      (node (ref "TS7500") (pin "8") (pinfunction "1_8") (pintype "passive"))
    )
    (net (code "103") (name "unconnected-(TS7500AR-1-Pad9)") (class "Default")
      (node (ref "TS7500") (pin "9") (pinfunction "1_9") (pintype "passive"))
    )
    (net (code "104") (name "unconnected-(TS7500C-1-Pad11)") (class "Default")
      (node (ref "TS7500") (pin "11") (pinfunction "1_11") (pintype "passive"))
    )
    (net (code "105") (name "unconnected-(TS7500E-1-Pad13)") (class "Default")
      (node (ref "TS7500") (pin "13") (pinfunction "1_13") (pintype "passive"))
    )
    (net (code "106") (name "unconnected-(TS7500K-1-Pad19)") (class "Default")
      (node (ref "TS7500") (pin "19") (pinfunction "1_19") (pintype "passive"))
    )
    (net (code "107") (name "unconnected-(TS7500L-1-Pad2)") (class "Default")
      (node (ref "TS7500") (pin "2") (pinfunction "1_2") (pintype "passive"))
    )
    (net (code "108") (name "unconnected-(TS7500M-1-Pad20)") (class "Default")
      (node (ref "TS7500") (pin "20") (pinfunction "1_20") (pintype "passive"))
    )
    (net (code "109") (name "unconnected-(TS7500N-1-Pad21)") (class "Default")
      (node (ref "TS7500") (pin "21") (pinfunction "1_21") (pintype "passive"))
    )
    (net (code "110") (name "unconnected-(TS7500O-1-Pad22)") (class "Default")
      (node (ref "TS7500") (pin "22") (pinfunction "1_22") (pintype "passive"))
    )
    (net (code "111") (name "unconnected-(TS7500P-1-Pad23)") (class "Default")
      (node (ref "TS7500") (pin "23") (pinfunction "1_23") (pintype "passive"))
    )
    (net (code "112") (name "unconnected-(TS7500Q-1-Pad24)") (class "Default")
      (node (ref "TS7500") (pin "24") (pinfunction "1_24") (pintype "passive"))
    )
    (net (code "113") (name "unconnected-(TS7500R-1-Pad25)") (class "Default")
      (node (ref "TS7500") (pin "25") (pinfunction "1_25") (pintype "passive"))
    )
    (net (code "114") (name "unconnected-(TS7500T-1-Pad27)") (class "Default")
      (node (ref "TS7500") (pin "27") (pinfunction "1_27") (pintype "passive"))
    )
    (net (code "115") (name "unconnected-(TS7500U-1-Pad28)") (class "Default")
      (node (ref "TS7500") (pin "28") (pinfunction "1_28") (pintype "passive"))
    )
    (net (code "116") (name "unconnected-(TS7500V-1-Pad29)") (class "Default")
      (node (ref "TS7500") (pin "29") (pinfunction "1_29") (pintype "passive"))
    )
    (net (code "117") (name "unconnected-(TS7500W-1-Pad3)") (class "Default")
      (node (ref "TS7500") (pin "3") (pinfunction "1_3") (pintype "passive"))
    )
    (net (code "118") (name "unconnected-(TS7500X-1-Pad30)") (class "Default")
      (node (ref "TS7500") (pin "30") (pinfunction "1_30") (pintype "passive"))
    )
    (net (code "119") (name "unconnected-(TS7500Y-1-Pad31)") (class "Default")
      (node (ref "TS7500") (pin "31") (pinfunction "1_31") (pintype "passive"))
    )
    (net (code "120") (name "unconnected-(USBB-PadVBUS)") (class "Default")
      (node (ref "USBB") (pin "VBUS") (pinfunction "VBUS_VBUS") (pintype "bidirectional"))
    )
  )
)
